# rtc_blk_-_Copy.net
KiCad netlist of a schematic drawn in Altium Designer
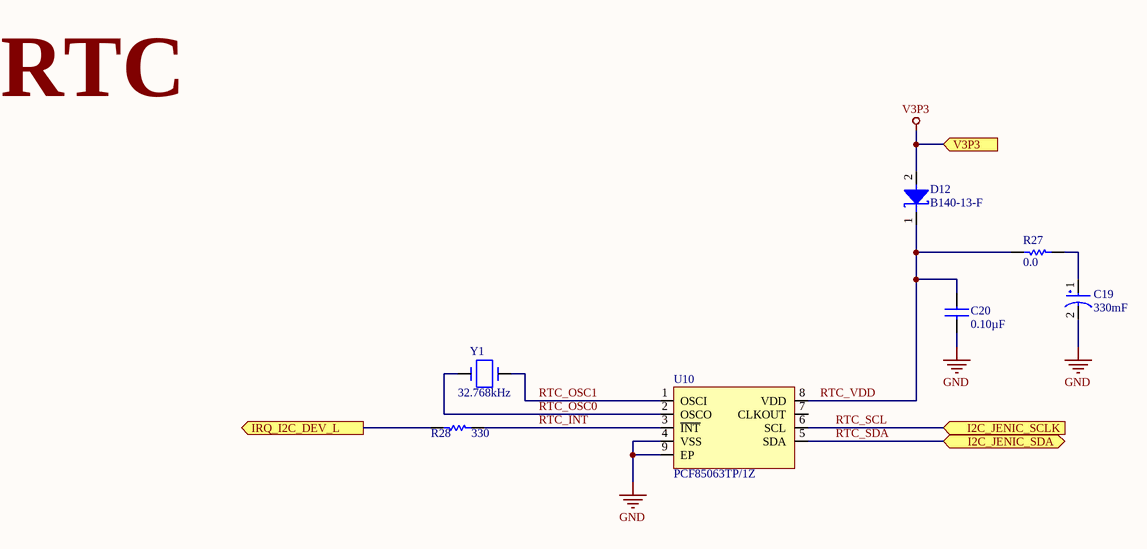
[diagram p0: rtc_blk - Copy.SchDoc]

(export (version "E")
  (design (tool "Eeschema 10.0.6"))
  (components
    (comp (ref "C19")
      (value "330mF")
      (footprint "ELNA_DSK-3R3H334T-HL")
      (description "CAP 330MF -20% +80% 3.3V SMD")
      (fields (field (name "MPN") "DSK-3R3H334T-HL"))
      (libsource (lib "Capacitor") (part "DSK-3R3H334T-HL"))
    )
    (comp (ref "C20")
      (value "0.10µF")
      (footprint "C0402")
      (description "CAP CER 0.1UF 50V X7R 0402")
      (fields (field (name "MPN") "GRM155R71H104ME14D"))
      (libsource (lib "Capacitor") (part "GRM155R71H104ME14D"))
    )
    (comp (ref "D12")
      (value "B140-13-F")
      (footprint "DO-214AC, SMA")
      (description "DIODE SCHOTTKY 40V 1A SMA")
      (libsource (lib "Diode") (part "B140-13-F"))
    )
    (comp (ref "R27")
      (value "0.0")
      (footprint "R0402")
      (description "RES SMD 0.0OHM JUMPER 1/16W 0402")
      (fields (field (name "MPN") "CRCW04020000Z0ED"))
      (libsource (lib "Res") (part "CRCW04020000Z0ED"))
    )
    (comp (ref "R28")
      (value "330")
      (footprint "R0402")
      (description "RES SMD 330 OHM 1% 1/16W 0402")
      (fields (field (name "MPN") "CRCW0402330RFKED"))
      (libsource (lib "Res") (part "CRCW0402330RFKED"))
    )
    (comp (ref "U10")
      (value "PCF85063TP/1Z")
      (footprint "SON9P50_200X300X80L40X24T150N")
      (description "Real Time Clock Serial 8-Pin HWSON EP")
      (fields (field (name "MPN") "PCF85063TP/1Z"))
      (libsource (lib "IC") (part "PCF85063TP/1Z"))
    )
    (comp (ref "Y1")
      (value "32.768kHz")
      (footprint "XTAL320X150X80L75X150N")
      (description "CRYSTAL 32.7680 KHZ 7.0PF SMD")
      (fields (field (name "MPN") "FC-13532.7680KA-AG5"))
      (libsource (lib "Crystal") (part "FC-13532.7680KA-AG5"))
    )
  )
  (nets
    (net (code "1") (name "/IRQ_I2C_DEV_L") (class "Default")
      (node (ref "R28") (pin "2") (pinfunction "2_2") (pintype "passive"))
    )
    (net (code "2") (name "/RTC_INT") (class "Default")
      (node (ref "R28") (pin "1") (pinfunction "1_1") (pintype "passive"))
      (node (ref "U10") (pin "3") (pinfunction "~{INT}_3") (pintype "passive"))
    )
    (net (code "3") (name "/RTC_OSC0") (class "Default")
      (node (ref "U10") (pin "2") (pinfunction "OSCO_2") (pintype "passive"))
      (node (ref "Y1") (pin "1") (pinfunction "1_1") (pintype "passive"))
    )
    (net (code "4") (name "/RTC_OSC1") (class "Default")
      (node (ref "U10") (pin "1") (pinfunction "OSCI_1") (pintype "passive"))
      (node (ref "Y1") (pin "2") (pinfunction "2_2") (pintype "passive"))
    )
    (net (code "5") (name "/RTC_SCL") (class "Default")
      (node (ref "U10") (pin "6") (pinfunction "SCL_6") (pintype "passive"))
    )
    (net (code "6") (name "/RTC_SDA") (class "Default")
      (node (ref "U10") (pin "5") (pinfunction "SDA_5") (pintype "passive"))
    )
    (net (code "7") (name "/RTC_VDD") (class "Default")
      (node (ref "C20") (pin "1") (pinfunction "1_1") (pintype "passive"))
      (node (ref "D12") (pin "1") (pinfunction "cathode_1") (pintype "passive"))
      (node (ref "R27") (pin "1") (pinfunction "1_1") (pintype "passive"))
      (node (ref "U10") (pin "8") (pinfunction "VDD_8") (pintype "passive"))
    )
    (net (code "8") (name "GND") (class "Default")
      (node (ref "C19") (pin "2") (pinfunction "2_2") (pintype "passive"))
      (node (ref "C20") (pin "2") (pinfunction "2_2") (pintype "passive"))
      (node (ref "U10") (pin "4") (pinfunction "VSS_4") (pintype "passive"))
      (node (ref "U10") (pin "9") (pinfunction "EP_9") (pintype "passive"))
    )
    (net (code "9") (name "Net-(C19-Pad1)") (class "Default")
      (node (ref "C19") (pin "1") (pinfunction "1_1") (pintype "passive"))
      (node (ref "R27") (pin "2") (pinfunction "2_2") (pintype "passive"))
    )
    (net (code "10") (name "V3P3") (class "Default")
      (node (ref "D12") (pin "2") (pinfunction "anode_2") (pintype "passive"))
    )
    (net (code "11") (name "unconnected-(U10-CLKOUT-Pad7)") (class "Default")
      (node (ref "U10") (pin "7") (pinfunction "CLKOUT_7") (pintype "passive"))
    )
  )
)
